# Emitter_Amplifier.net
KiCad netlist of a schematic drawn in Altium Designer
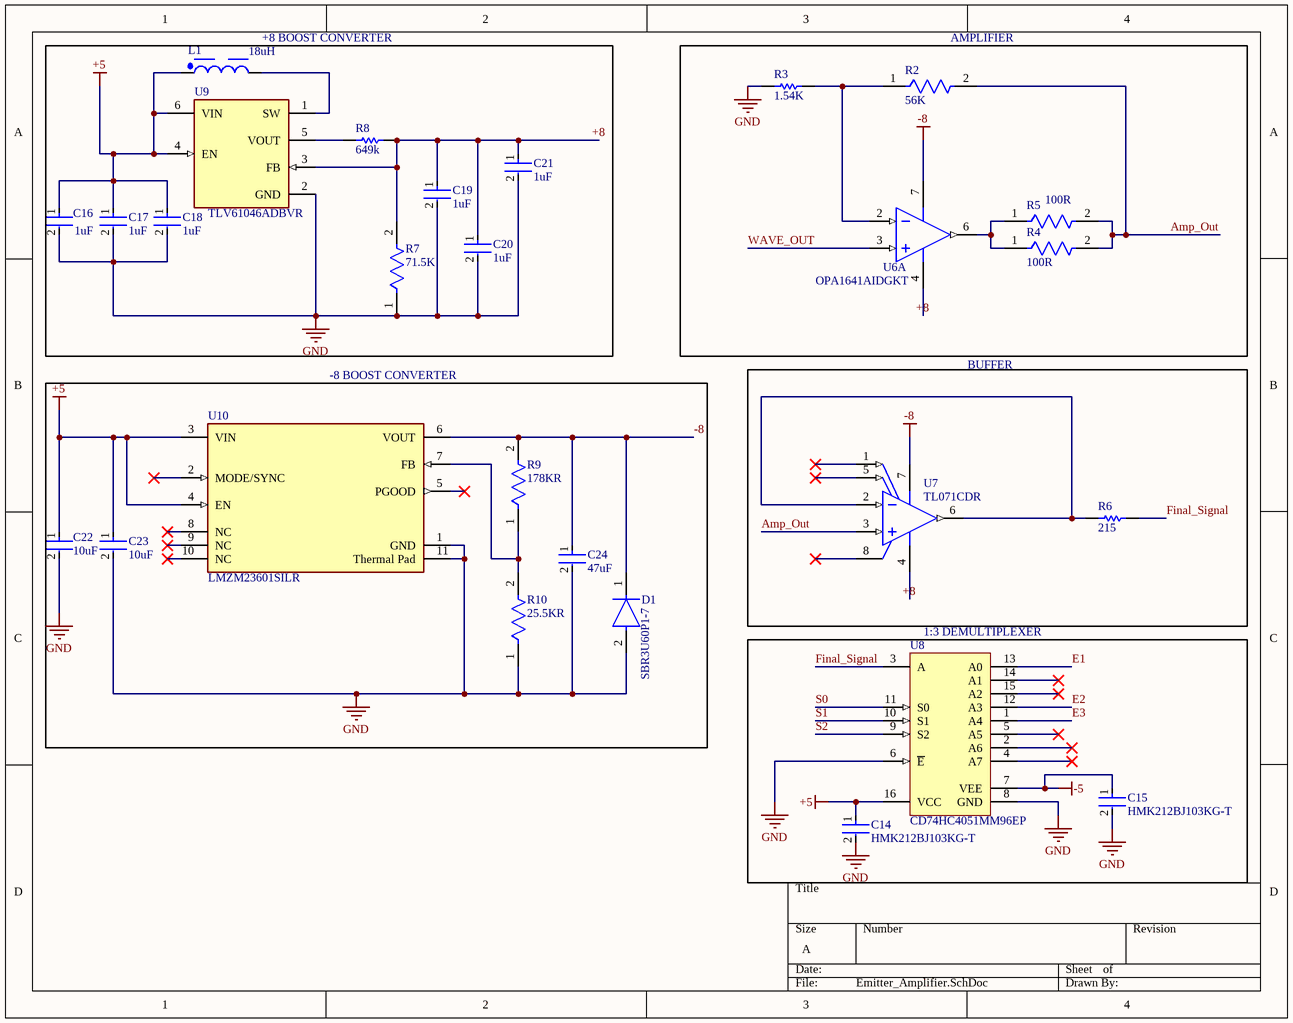
[diagram p0: Emitter_Amplifier.SchDoc]

(export (version "E")
  (design (tool "Eeschema 10.0.6"))
  (components
    (comp (ref "C14")
      (value "HMK212BJ103KG-T")
      (footprint "FP-0805-L_2_0_0_1-W_1_25-IPC_B")
      (description "Multilayer Ceramic Capacitor 0.01 uF 100V B 10% SMD 0805 T/R")
      (fields (field (name "VOLTAGE") "100V") (field (name "TOLERANCE") "10%"))
      (libsource (lib "Altium Content Vault") (part "b4654b650e69147ec39a6b967a45e02"))
    )
    (comp (ref "C15")
      (value "HMK212BJ103KG-T")
      (footprint "FP-0805-L_2_0_0_1-W_1_25-IPC_B")
      (description "Multilayer Ceramic Capacitor 0.01 uF 100V B 10% SMD 0805 T/R")
      (fields (field (name "VOLTAGE") "100V") (field (name "TOLERANCE") "10%"))
      (libsource (lib "Altium Content Vault") (part "b4654b650e69147ec39a6b967a45e02"))
    )
    (comp (ref "C16")
      (value "1uF")
      (footprint "FP-0603-L_1_6_0_1-W_0_8_0-IPC_C")
      (description "None")
      (fields (field (name "TOLERANCE") "10%"))
      (libsource (lib "Altium Content Vault") (part "02cd4be3c70576c341d710602a673aa"))
    )
    (comp (ref "C17")
      (value "1uF")
      (footprint "FP-0603-L_1_6_0_1-W_0_8_0-IPC_C")
      (description "None")
      (fields (field (name "TOLERANCE") "10%"))
      (libsource (lib "Altium Content Vault") (part "02cd4be3c70576c341d710602a673aa"))
    )
    (comp (ref "C18")
      (value "1uF")
      (footprint "FP-0603-L_1_6_0_1-W_0_8_0-IPC_C")
      (description "None")
      (fields (field (name "TOLERANCE") "10%"))
      (libsource (lib "Altium Content Vault") (part "02cd4be3c70576c341d710602a673aa"))
    )
    (comp (ref "C19")
      (value "1uF")
      (footprint "FP-0603-L_1_6_0_1-W_0_8_0-IPC_C")
      (description "None")
      (fields (field (name "TOLERANCE") "10%"))
      (libsource (lib "Altium Content Vault") (part "02cd4be3c70576c341d710602a673aa"))
    )
    (comp (ref "C20")
      (value "1uF")
      (footprint "FP-0603-L_1_6_0_1-W_0_8_0-IPC_C")
      (description "None")
      (fields (field (name "TOLERANCE") "10%"))
      (libsource (lib "Altium Content Vault") (part "02cd4be3c70576c341d710602a673aa"))
    )
    (comp (ref "C21")
      (value "1uF")
      (footprint "FP-0603-L_1_6_0_1-W_0_8_0-IPC_C")
      (description "None")
      (fields (field (name "TOLERANCE") "10%"))
      (libsource (lib "Altium Content Vault") (part "02cd4be3c70576c341d710602a673aa"))
    )
    (comp (ref "C22")
      (value "10uF")
      (footprint "FP-GRM21B-0_15-IPC_A")
      (description "Chip Multilayer Ceramic Capacitors for General Purpose, 0805, 10uF, X5R, 15%, 20%, 25V")
      (fields (field (name "TOLERANCE") "20%"))
      (libsource (lib "Altium Content Vault") (part "b4654b650e69147ec39a6b967a45e02"))
    )
    (comp (ref "C23")
      (value "10uF")
      (footprint "FP-0805-L_2_0_0_2-W_1_25-IPC_A")
      (description "Multilayer Ceramic Capacitor 10uF 35V X5R 10% SMD 0805 T/R")
      (fields (field (name "TOLERANCE") "10%"))
      (libsource (lib "Altium Content Vault") (part "02cd4be3c70576c341d710602a673aa"))
    )
    (comp (ref "C24")
      (value "47uF")
      (footprint "FP-GRM32E-0_3-0_2-IPC_C")
      (description "CAP CER 47UF 16V X5R 1210")
      (fields (field (name "VOLTAGE") "16V") (field (name "TOLERANCE") "10%"))
      (libsource (lib "Altium Content Vault") (part "b4654b650e69147ec39a6b967a45e02"))
    )
    (comp (ref "D1")
      (value "SBR3U60P1-7")
      (footprint "FP-PowerDI123-MFG")
      (description "DIODE SBR 60V 3A POWERDI123")
      (fields
        (field (name "MANUFACTURER") "Diodes Inc.")
        (field (name "OCTOPART") "https://octopart.com/sbr3u60p1-7-diodes+inc.-21328922")
      )
      (libsource (lib "Altium Content Vault") (part "d7152d700b627762746794eb795d46e"))
    )
    (comp (ref "L1")
      (value "18uH")
      (footprint "WE-PD2_5848")
      (libsource (lib "Altium Content Vault") (part "Inductor - 2"))
    )
    (comp (ref "R2")
      (value "56K")
      (footprint "FP-MCR10-IPC_C")
      (description "Thick Film Chip Resistor, 0805, 56kΩ, 5%, 200ppm/°C, 0.125W, 150V")
      (fields (field (name "TOLERANCE") "5%"))
      (libsource (lib "Altium Content Vault") (part "1029c3af85768c4190bb7ad29bc67b5"))
    )
    (comp (ref "R3")
      (value "1.54K")
      (footprint "RESC2013X70X40LL20T20")
      (fields (field (name "MANUFACTURER") "Panasonic") (field (name "PART NUMBER") "ERJ-6ENF1541V"))
      (libsource (lib "Altium Content Vault") (part "RES"))
    )
    (comp (ref "R4")
      (value "100R")
      (footprint "FP-ERJ6EN-MFG")
      (description "RES SMD 100 OHM 1% 1/8W 0805")
      (fields (field (name "TOLERANCE") "1%"))
      (libsource (lib "Altium Content Vault") (part "1029c3af85768c4190bb7ad29bc67b5"))
    )
    (comp (ref "R5")
      (value "100R")
      (footprint "FP-ERJ6EN-MFG")
      (description "RES SMD 100 OHM 1% 1/8W 0805")
      (fields (field (name "TOLERANCE") "1%"))
      (libsource (lib "Altium Content Vault") (part "1029c3af85768c4190bb7ad29bc67b5"))
    )
    (comp (ref "R6")
      (value "215")
      (footprint "RESC2013X70X40NL20T20")
      (fields (field (name "MANUFACTURER") "Panasonic") (field (name "PART NUMBER") "ERJ-6ENF2150V"))
      (libsource (lib "Altium Content Vault") (part "RES"))
    )
    (comp (ref "R7")
      (value "71.5K")
      (footprint "FP-RG2012-MFG")
      (description "Automotive Metal Thin Film Chip Resistor, 0805, 71.5kΩ, 0.5%, 25ppm/°C, 0.125W, 150V")
      (fields (field (name "TOLERANCE") "0.5%"))
      (libsource (lib "Altium Content Vault") (part "1029c3af85768c4190bb7ad29bc67b5"))
    )
    (comp (ref "R8")
      (value "649k")
      (footprint "RESC2013X70X40ML20T20")
      (fields (field (name "MANUFACTURER") "Panasonic") (field (name "PART NUMBER") "ERJ-6ENF6493V"))
      (libsource (lib "Altium Content Vault") (part "RES"))
    )
    (comp (ref "R9")
      (value "178KR")
      (footprint "FP-CR0805-IPC_C")
      (description "Thick Film Chip Resistors 0805 178kΩ 0.125W 1% 100ppm/°C")
      (fields (field (name "TOLERANCE") "1%"))
      (libsource (lib "Altium Content Vault") (part "1029c3af85768c4190bb7ad29bc67b5"))
    )
    (comp (ref "R10")
      (value "25.5KR")
      (footprint "FP-CRCW0805-e3-IPC_A")
      (description "RES Thick Film, 25.5kΩ, 1%, 0.125W, 100ppm/°C, 0805")
      (fields (field (name "TOLERANCE") "1%"))
      (libsource (lib "Altium Content Vault") (part "1029c3af85768c4190bb7ad29bc67b5"))
    )
    (comp (ref "U6")
      (value "OPA1641AIDGKT")
      (footprint "DGK0008A_N")
      (fields (field (name "MANUFACTURER") "Texas Instruments"))
      (libsource (lib "Altium Content Vault") (part "TI-OPA1641DGK8"))
    )
    (comp (ref "U7")
      (value "TL071CDR")
      (footprint "D0008A_M")
      (fields (field (name "MANUFACTURER") "Texas Instruments"))
      (libsource (lib "Altium Content Vault") (part "TI-AMP-S5-2-8"))
    )
    (comp (ref "U8")
      (value "CD74HC4051MM96EP")
      (footprint "D0016A_L")
      (description "Enhanced Product High Speed Cmos Logic Analog Multiplexers/Demultiplexers, D0016A, LARGE T&R")
      (fields
        (field (name "MANUFACTURER") "Texas Instruments")
        (field (name "GENERIC PART NUMBER") "CD74HC4051-EP")
      )
      (libsource (lib "Altium Content Vault") (part "TI-CDX4HCX4051-16"))
    )
    (comp (ref "U9")
      (value "TLV61046ADBVR")
      (footprint "FP-DBV0006A-MFG")
      (description "IC REG BOOST ADJ SOT23-6")
      (fields
        (field (name "MANUFACTURER") "Texas Instruments")
        (field (name "OCTOPART") "https://octopart.com/tlv61046adbvr-texas+instruments-81856326")
      )
      (libsource (lib "Altium Content Vault") (part "b8ee0be35f9915b5d65b82546c9a9cd"))
    )
    (comp (ref "U10")
      (value "LMZM23601SILR")
      (footprint "FP-SIL0010A-MFG")
      (description "DC DC CONVERTER 1.2-15V")
      (libsource (lib "Altium Content Vault") (part "0e66294c665cedcb0cad0e76d0c9cff"))
    )
  )
  (nets
    (net (code "1") (name "+5") (class "Default")
      (node (ref "C14") (pin "1") (pinfunction "1_1") (pintype "passive"))
      (node (ref "C16") (pin "1") (pinfunction "1_1") (pintype "passive"))
      (node (ref "C17") (pin "1") (pinfunction "1_1") (pintype "passive"))
      (node (ref "C18") (pin "1") (pinfunction "1_1") (pintype "passive"))
      (node (ref "C22") (pin "1") (pinfunction "1_1") (pintype "passive"))
      (node (ref "C23") (pin "1") (pinfunction "1_1") (pintype "passive"))
      (node (ref "L1") (pin "1") (pinfunction "1_1") (pintype "passive"))
      (node (ref "U10") (pin "3") (pinfunction "VIN_3") (pintype "power_in"))
      (node (ref "U10") (pin "4") (pinfunction "EN_4") (pintype "input"))
      (node (ref "U8") (pin "16") (pinfunction "VCC_16") (pintype "power_in"))
      (node (ref "U9") (pin "4") (pinfunction "EN_4") (pintype "input"))
      (node (ref "U9") (pin "6") (pinfunction "VIN_6") (pintype "power_in"))
    )
    (net (code "2") (name "-5") (class "Default")
      (node (ref "C15") (pin "1") (pinfunction "1_1") (pintype "passive"))
      (node (ref "U8") (pin "7") (pinfunction "VEE_7") (pintype "power_in"))
    )
    (net (code "3") (name "-8") (class "Default")
      (node (ref "C24") (pin "1") (pinfunction "1_1") (pintype "passive"))
      (node (ref "D1") (pin "1") (pinfunction "C_1") (pintype "passive"))
      (node (ref "R9") (pin "2") (pinfunction "2_2") (pintype "passive"))
      (node (ref "U10") (pin "6") (pinfunction "VOUT_6") (pintype "power_in"))
      (node (ref "U6") (pin "7") (pinfunction "V+_7") (pintype "power_in"))
      (node (ref "U7") (pin "7") (pinfunction "VCC+_7") (pintype "power_in"))
    )
    (net (code "4") (name "/+8") (class "Default")
      (node (ref "C19") (pin "1") (pinfunction "1_1") (pintype "passive"))
      (node (ref "C20") (pin "1") (pinfunction "1_1") (pintype "passive"))
      (node (ref "C21") (pin "1") (pinfunction "1_1") (pintype "passive"))
      (node (ref "R7") (pin "2") (pinfunction "2_2") (pintype "passive"))
      (node (ref "R8") (pin "1") (pinfunction "1_1") (pintype "passive"))
      (node (ref "U6") (pin "4") (pinfunction "V-_4") (pintype "power_in"))
      (node (ref "U7") (pin "4") (pinfunction "VCC-_4") (pintype "power_in"))
      (node (ref "U9") (pin "3") (pinfunction "FB_3") (pintype "input"))
    )
    (net (code "5") (name "/Amp_Out") (class "Default")
      (node (ref "R2") (pin "2") (pinfunction "2_2") (pintype "passive"))
      (node (ref "R4") (pin "2") (pinfunction "2_2") (pintype "passive"))
      (node (ref "R5") (pin "2") (pinfunction "2_2") (pintype "passive"))
      (node (ref "U7") (pin "3") (pinfunction "IN+_3") (pintype "input"))
    )
    (net (code "6") (name "/E1") (class "Default")
      (node (ref "U8") (pin "13") (pinfunction "A0_13") (pintype "passive"))
    )
    (net (code "7") (name "/E2") (class "Default")
      (node (ref "U8") (pin "12") (pinfunction "A3_12") (pintype "passive"))
    )
    (net (code "8") (name "/E3") (class "Default")
      (node (ref "U8") (pin "1") (pinfunction "A4_1") (pintype "passive"))
    )
    (net (code "9") (name "/Final_Signal") (class "Default")
      (node (ref "R6") (pin "2") (pinfunction "2_2") (pintype "passive"))
      (node (ref "U8") (pin "3") (pinfunction "A_3") (pintype "passive"))
    )
    (net (code "10") (name "/S0") (class "Default")
      (node (ref "U8") (pin "11") (pinfunction "S0_11") (pintype "input"))
    )
    (net (code "11") (name "/S1") (class "Default")
      (node (ref "U8") (pin "10") (pinfunction "S1_10") (pintype "input"))
    )
    (net (code "12") (name "/S2") (class "Default")
      (node (ref "U8") (pin "9") (pinfunction "S2_9") (pintype "input"))
    )
    (net (code "13") (name "/WAVE_OUT") (class "Default")
      (node (ref "U6") (pin "3") (pinfunction "IN+_3") (pintype "input"))
    )
    (net (code "14") (name "GND") (class "Default")
      (node (ref "C14") (pin "2") (pinfunction "2_2") (pintype "passive"))
      (node (ref "C15") (pin "2") (pinfunction "2_2") (pintype "passive"))
      (node (ref "C16") (pin "2") (pinfunction "2_2") (pintype "passive"))
      (node (ref "C17") (pin "2") (pinfunction "2_2") (pintype "passive"))
      (node (ref "C18") (pin "2") (pinfunction "2_2") (pintype "passive"))
      (node (ref "C19") (pin "2") (pinfunction "2_2") (pintype "passive"))
      (node (ref "C20") (pin "2") (pinfunction "2_2") (pintype "passive"))
      (node (ref "C21") (pin "2") (pinfunction "2_2") (pintype "passive"))
      (node (ref "C22") (pin "2") (pinfunction "2_2") (pintype "passive"))
      (node (ref "C23") (pin "2") (pinfunction "2_2") (pintype "passive"))
      (node (ref "C24") (pin "2") (pinfunction "2_2") (pintype "passive"))
      (node (ref "D1") (pin "2") (pinfunction "A_2") (pintype "passive"))
      (node (ref "R10") (pin "1") (pinfunction "1_1") (pintype "passive"))
      (node (ref "R3") (pin "1") (pinfunction "1_1") (pintype "passive"))
      (node (ref "R7") (pin "1") (pinfunction "1_1") (pintype "passive"))
      (node (ref "U10") (pin "1") (pinfunction "GND_1") (pintype "power_in"))
      (node (ref "U10") (pin "11") (pinfunction "Thermal_Pad_11") (pintype "power_in"))
      (node (ref "U8") (pin "6") (pinfunction "~{E}_6") (pintype "input"))
      (node (ref "U8") (pin "8") (pinfunction "GND_8") (pintype "power_in"))
      (node (ref "U9") (pin "2") (pinfunction "GND_2") (pintype "power_in"))
    )
    (net (code "15") (name "Net-(U6A-IN-)") (class "Default")
      (node (ref "R2") (pin "1") (pinfunction "1_1") (pintype "passive"))
      (node (ref "R3") (pin "2") (pinfunction "2_2") (pintype "passive"))
      (node (ref "U6") (pin "2") (pinfunction "IN-_2") (pintype "input"))
    )
    (net (code "16") (name "Net-(U6A-OUT)") (class "Default")
      (node (ref "R4") (pin "1") (pinfunction "1_1") (pintype "passive"))
      (node (ref "R5") (pin "1") (pinfunction "1_1") (pintype "passive"))
      (node (ref "U6") (pin "6") (pinfunction "OUT_6") (pintype "output"))
    )
    (net (code "17") (name "Net-(U7-IN-)") (class "Default")
      (node (ref "R6") (pin "1") (pinfunction "1_1") (pintype "passive"))
      (node (ref "U7") (pin "2") (pinfunction "IN-_2") (pintype "input"))
      (node (ref "U7") (pin "6") (pinfunction "OUT_6") (pintype "output"))
    )
    (net (code "18") (name "Net-(U9-SW)") (class "Default")
      (node (ref "L1") (pin "2") (pinfunction "2_2") (pintype "passive"))
      (node (ref "U9") (pin "1") (pinfunction "SW_1") (pintype "power_in"))
    )
    (net (code "19") (name "Net-(U9-VOUT)") (class "Default")
      (node (ref "R8") (pin "2") (pinfunction "2_2") (pintype "passive"))
      (node (ref "U9") (pin "5") (pinfunction "VOUT_5") (pintype "power_in"))
    )
    (net (code "20") (name "Net-(U10-FB)") (class "Default")
      (node (ref "R10") (pin "2") (pinfunction "2_2") (pintype "passive"))
      (node (ref "R9") (pin "1") (pinfunction "1_1") (pintype "passive"))
      (node (ref "U10") (pin "7") (pinfunction "FB_7") (pintype "input"))
    )
    (net (code "21") (name "unconnected-(U7-NC-Pad8)") (class "Default")
      (node (ref "U7") (pin "8") (pinfunction "NC_8") (pintype "passive+no_connect"))
    )
    (net (code "22") (name "unconnected-(U7-OFFSET_N1-Pad1)") (class "Default")
      (node (ref "U7") (pin "1") (pinfunction "OFFSET_N1_1") (pintype "input+no_connect"))
    )
    (net (code "23") (name "unconnected-(U7-OFFSET_N2-Pad5)") (class "Default")
      (node (ref "U7") (pin "5") (pinfunction "OFFSET_N2_5") (pintype "input+no_connect"))
    )
    (net (code "24") (name "unconnected-(U8-A1-Pad14)") (class "Default")
      (node (ref "U8") (pin "14") (pinfunction "A1_14") (pintype "passive+no_connect"))
    )
    (net (code "25") (name "unconnected-(U8-A2-Pad15)") (class "Default")
      (node (ref "U8") (pin "15") (pinfunction "A2_15") (pintype "passive+no_connect"))
    )
    (net (code "26") (name "unconnected-(U8-A5-Pad5)") (class "Default")
      (node (ref "U8") (pin "5") (pinfunction "A5_5") (pintype "passive+no_connect"))
    )
    (net (code "27") (name "unconnected-(U8-A6-Pad2)") (class "Default")
      (node (ref "U8") (pin "2") (pinfunction "A6_2") (pintype "passive+no_connect"))
    )
    (net (code "28") (name "unconnected-(U8-A7-Pad4)") (class "Default")
      (node (ref "U8") (pin "4") (pinfunction "A7_4") (pintype "passive+no_connect"))
    )
    (net (code "29") (name "unconnected-(U10-MODE{slash}SYNC-Pad2)") (class "Default")
      (node (ref "U10") (pin "2") (pinfunction "MODE/SYNC_2") (pintype "input+no_connect"))
    )
    (net (code "30") (name "unconnected-(U10-NC-Pad8)") (class "Default")
      (node (ref "U10") (pin "8") (pinfunction "NC_8") (pintype "passive+no_connect"))
    )
    (net (code "31") (name "unconnected-(U10-NC-Pad9)") (class "Default")
      (node (ref "U10") (pin "9") (pinfunction "NC_9") (pintype "passive+no_connect"))
    )
    (net (code "32") (name "unconnected-(U10-NC-Pad10)") (class "Default")
      (node (ref "U10") (pin "10") (pinfunction "NC_10") (pintype "passive+no_connect"))
    )
    (net (code "33") (name "unconnected-(U10-PGOOD-Pad5)") (class "Default")
      (node (ref "U10") (pin "5") (pinfunction "PGOOD_5") (pintype "output+no_connect"))
    )
  )
)
